# S202X.net
KiCad netlist of a schematic drawn in EAGLE
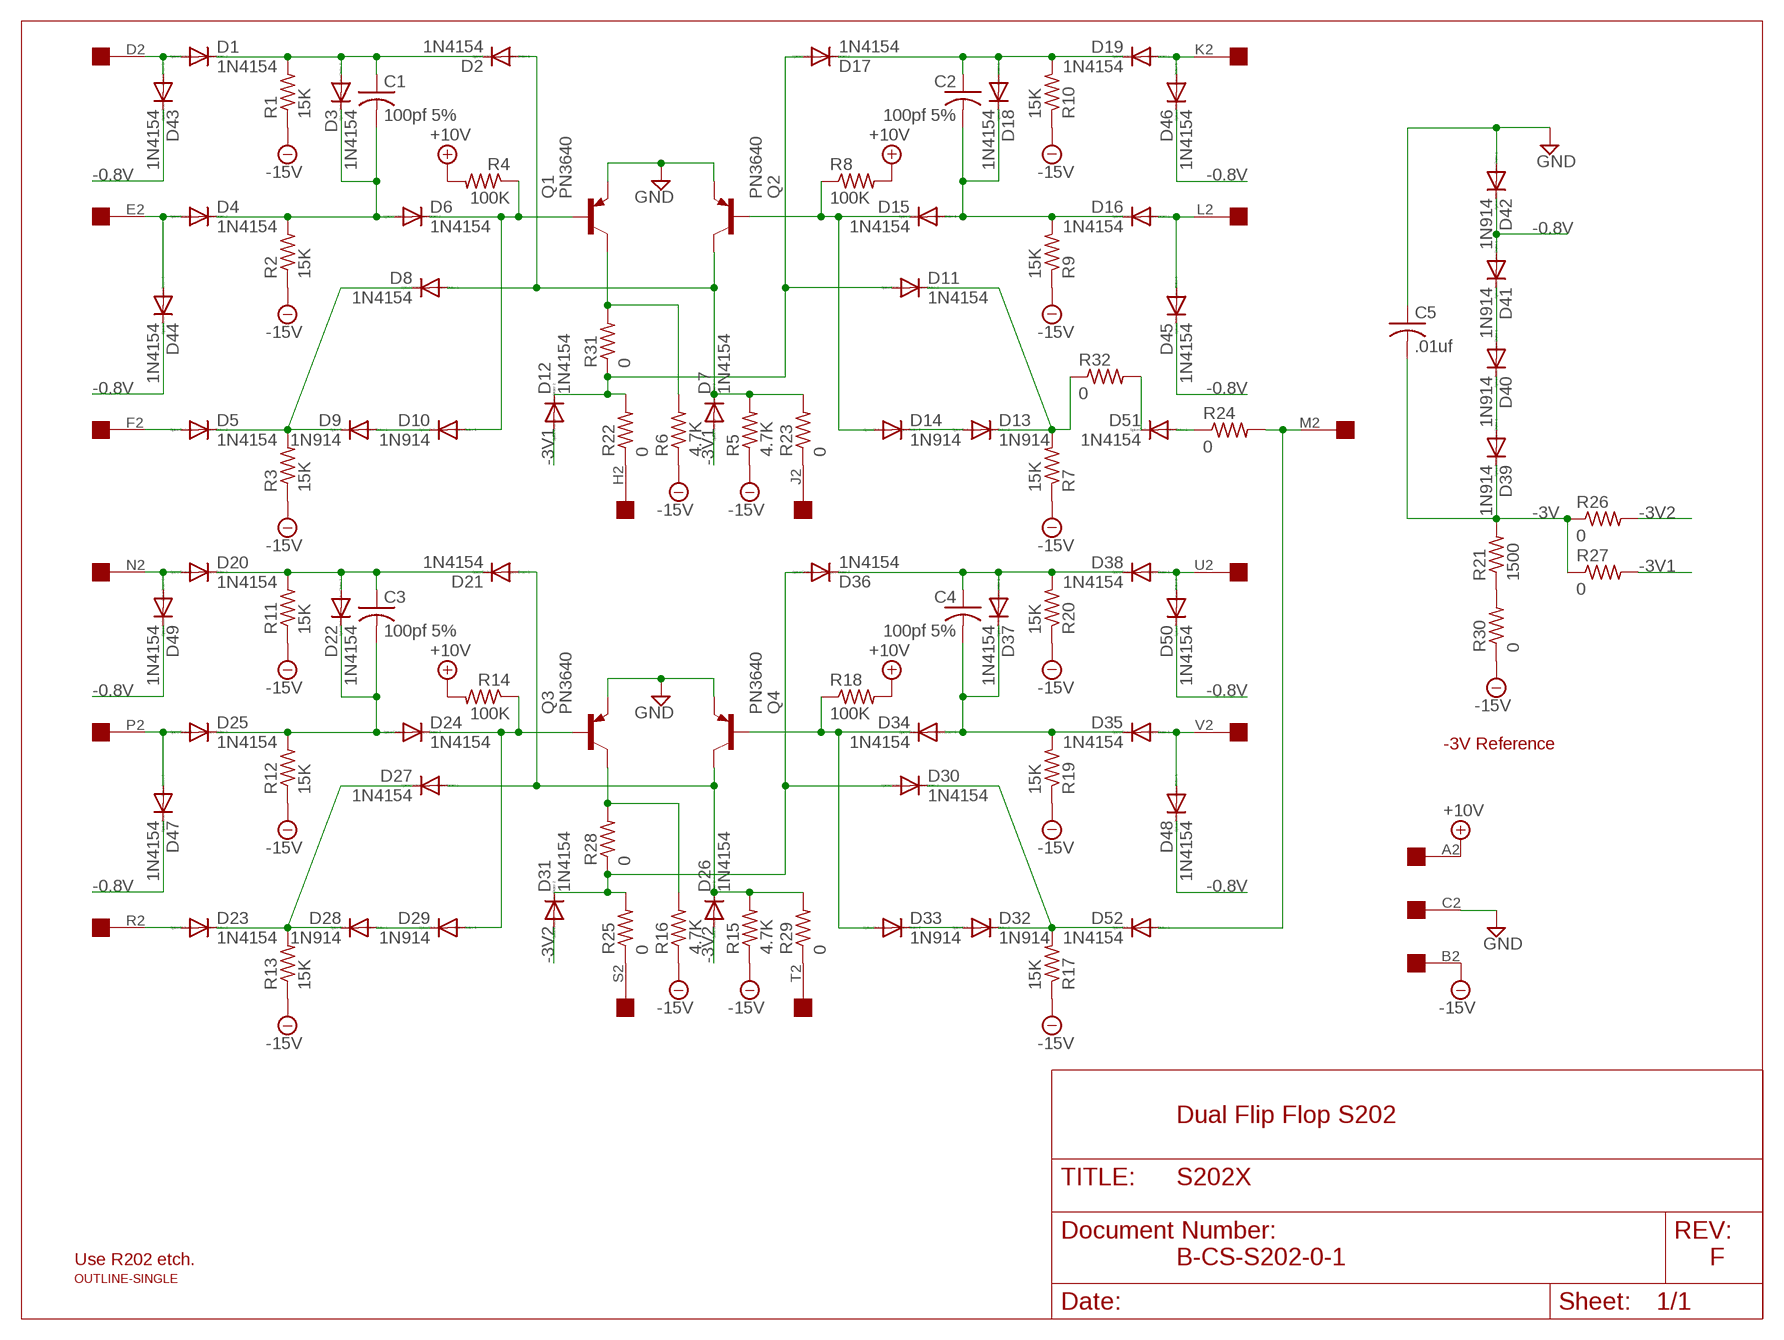
[diagram p0: schematic, sheet 1]

(export (version "E")
  (design (tool "Eeschema 10.0.6"))
  (components
    (comp (ref "C1")
      (value "100pf 5%")
      (footprint "eagle-import:C050-025X075")
      (libsource (lib "eagle-import") (part "C-US050-025X075"))
    )
    (comp (ref "C2")
      (value "100pf 5%")
      (footprint "eagle-import:C050-025X075")
      (libsource (lib "eagle-import") (part "C-US050-025X075"))
    )
    (comp (ref "C3")
      (value "100pf 5%")
      (footprint "eagle-import:C050-025X075")
      (libsource (lib "eagle-import") (part "C-US050-025X075"))
    )
    (comp (ref "C4")
      (value "100pf 5%")
      (footprint "eagle-import:C050-025X075")
      (libsource (lib "eagle-import") (part "C-US050-025X075"))
    )
    (comp (ref "C5")
      (value ".01uf")
      (footprint "eagle-import:C050-025X075")
      (libsource (lib "eagle-import") (part "C-US050-025X075"))
    )
    (comp (ref "D1")
      (value "1N4154")
      (footprint "eagle-import:DO35-10")
      (libsource (lib "eagle-import") (part "1N4148DO35-10"))
    )
    (comp (ref "D2")
      (value "1N4154")
      (footprint "eagle-import:DO35-10")
      (libsource (lib "eagle-import") (part "1N4148DO35-10"))
    )
    (comp (ref "D3")
      (value "1N4154")
      (footprint "eagle-import:DO35-10")
      (libsource (lib "eagle-import") (part "1N4148DO35-10"))
    )
    (comp (ref "D4")
      (value "1N4154")
      (footprint "eagle-import:DO35-10")
      (libsource (lib "eagle-import") (part "1N4148DO35-10"))
    )
    (comp (ref "D5")
      (value "1N4154")
      (footprint "eagle-import:DO35-10")
      (libsource (lib "eagle-import") (part "1N4148DO35-10"))
    )
    (comp (ref "D6")
      (value "1N4154")
      (footprint "eagle-import:DO35-10")
      (libsource (lib "eagle-import") (part "1N4148DO35-10"))
    )
    (comp (ref "D7")
      (value "1N4154")
      (footprint "eagle-import:DO35-10")
      (libsource (lib "eagle-import") (part "1N4148DO35-10"))
    )
    (comp (ref "D8")
      (value "1N4154")
      (footprint "eagle-import:DO35-10")
      (libsource (lib "eagle-import") (part "1N4148DO35-10"))
    )
    (comp (ref "D9")
      (value "1N914")
      (footprint "eagle-import:DO35-10")
      (libsource (lib "eagle-import") (part "1N4148DO35-10"))
    )
    (comp (ref "D10")
      (value "1N914")
      (footprint "eagle-import:DO35-10")
      (libsource (lib "eagle-import") (part "1N4148DO35-10"))
    )
    (comp (ref "D11")
      (value "1N4154")
      (footprint "eagle-import:DO35-10")
      (libsource (lib "eagle-import") (part "1N4148DO35-10"))
    )
    (comp (ref "D12")
      (value "1N4154")
      (footprint "eagle-import:DO35-10")
      (libsource (lib "eagle-import") (part "1N4148DO35-10"))
    )
    (comp (ref "D13")
      (value "1N914")
      (footprint "eagle-import:DO35-10")
      (libsource (lib "eagle-import") (part "1N4148DO35-10"))
    )
    (comp (ref "D14")
      (value "1N914")
      (footprint "eagle-import:DO35-10")
      (libsource (lib "eagle-import") (part "1N4148DO35-10"))
    )
    (comp (ref "D15")
      (value "1N4154")
      (footprint "eagle-import:DO35-10")
      (libsource (lib "eagle-import") (part "1N4148DO35-10"))
    )
    (comp (ref "D16")
      (value "1N4154")
      (footprint "eagle-import:DO35-10")
      (libsource (lib "eagle-import") (part "1N4148DO35-10"))
    )
    (comp (ref "D17")
      (value "1N4154")
      (footprint "eagle-import:DO35-10")
      (libsource (lib "eagle-import") (part "1N4148DO35-10"))
    )
    (comp (ref "D18")
      (value "1N4154")
      (footprint "eagle-import:DO35-10")
      (libsource (lib "eagle-import") (part "1N4148DO35-10"))
    )
    (comp (ref "D19")
      (value "1N4154")
      (footprint "eagle-import:DO35-10")
      (libsource (lib "eagle-import") (part "1N4148DO35-10"))
    )
    (comp (ref "D20")
      (value "1N4154")
      (footprint "eagle-import:DO35-10")
      (libsource (lib "eagle-import") (part "1N4148DO35-10"))
    )
    (comp (ref "D21")
      (value "1N4154")
      (footprint "eagle-import:DO35-10")
      (libsource (lib "eagle-import") (part "1N4148DO35-10"))
    )
    (comp (ref "D22")
      (value "1N4154")
      (footprint "eagle-import:DO35-10")
      (libsource (lib "eagle-import") (part "1N4148DO35-10"))
    )
    (comp (ref "D23")
      (value "1N4154")
      (footprint "eagle-import:DO35-10")
      (libsource (lib "eagle-import") (part "1N4148DO35-10"))
    )
    (comp (ref "D24")
      (value "1N4154")
      (footprint "eagle-import:DO35-10")
      (libsource (lib "eagle-import") (part "1N4148DO35-10"))
    )
    (comp (ref "D25")
      (value "1N4154")
      (footprint "eagle-import:DO35-10")
      (libsource (lib "eagle-import") (part "1N4148DO35-10"))
    )
    (comp (ref "D26")
      (value "1N4154")
      (footprint "eagle-import:DO35-10")
      (libsource (lib "eagle-import") (part "1N4148DO35-10"))
    )
    (comp (ref "D27")
      (value "1N4154")
      (footprint "eagle-import:DO35-10")
      (libsource (lib "eagle-import") (part "1N4148DO35-10"))
    )
    (comp (ref "D28")
      (value "1N914")
      (footprint "eagle-import:DO35-10")
      (libsource (lib "eagle-import") (part "1N4148DO35-10"))
    )
    (comp (ref "D29")
      (value "1N914")
      (footprint "eagle-import:DO35-10")
      (libsource (lib "eagle-import") (part "1N4148DO35-10"))
    )
    (comp (ref "D30")
      (value "1N4154")
      (footprint "eagle-import:DO35-10")
      (libsource (lib "eagle-import") (part "1N4148DO35-10"))
    )
    (comp (ref "D31")
      (value "1N4154")
      (footprint "eagle-import:DO35-10")
      (libsource (lib "eagle-import") (part "1N4148DO35-10"))
    )
    (comp (ref "D32")
      (value "1N914")
      (footprint "eagle-import:DO35-10")
      (libsource (lib "eagle-import") (part "1N4148DO35-10"))
    )
    (comp (ref "D33")
      (value "1N914")
      (footprint "eagle-import:DO35-10")
      (libsource (lib "eagle-import") (part "1N4148DO35-10"))
    )
    (comp (ref "D34")
      (value "1N4154")
      (footprint "eagle-import:DO35-10")
      (libsource (lib "eagle-import") (part "1N4148DO35-10"))
    )
    (comp (ref "D35")
      (value "1N4154")
      (footprint "eagle-import:DO35-10")
      (libsource (lib "eagle-import") (part "1N4148DO35-10"))
    )
    (comp (ref "D36")
      (value "1N4154")
      (footprint "eagle-import:DO35-10")
      (libsource (lib "eagle-import") (part "1N4148DO35-10"))
    )
    (comp (ref "D37")
      (value "1N4154")
      (footprint "eagle-import:DO35-10")
      (libsource (lib "eagle-import") (part "1N4148DO35-10"))
    )
    (comp (ref "D38")
      (value "1N4154")
      (footprint "eagle-import:DO35-10")
      (libsource (lib "eagle-import") (part "1N4148DO35-10"))
    )
    (comp (ref "D39")
      (value "1N914")
      (footprint "eagle-import:DO35-10")
      (libsource (lib "eagle-import") (part "1N4148DO35-10"))
    )
    (comp (ref "D40")
      (value "1N914")
      (footprint "eagle-import:DO35-10")
      (libsource (lib "eagle-import") (part "1N4148DO35-10"))
    )
    (comp (ref "D41")
      (value "1N914")
      (footprint "eagle-import:DO35-10")
      (libsource (lib "eagle-import") (part "1N4148DO35-10"))
    )
    (comp (ref "D42")
      (value "1N914")
      (footprint "eagle-import:DO35-10")
      (libsource (lib "eagle-import") (part "1N4148DO35-10"))
    )
    (comp (ref "D43")
      (value "1N4154")
      (footprint "eagle-import:DO35-10")
      (libsource (lib "eagle-import") (part "1N4148DO35-10"))
    )
    (comp (ref "D44")
      (value "1N4154")
      (footprint "eagle-import:DO35-10")
      (libsource (lib "eagle-import") (part "1N4148DO35-10"))
    )
    (comp (ref "D45")
      (value "1N4154")
      (footprint "eagle-import:DO35-10")
      (libsource (lib "eagle-import") (part "1N4148DO35-10"))
    )
    (comp (ref "D46")
      (value "1N4154")
      (footprint "eagle-import:DO35-10")
      (libsource (lib "eagle-import") (part "1N4148DO35-10"))
    )
    (comp (ref "D47")
      (value "1N4154")
      (footprint "eagle-import:DO35-10")
      (libsource (lib "eagle-import") (part "1N4148DO35-10"))
    )
    (comp (ref "D48")
      (value "1N4154")
      (footprint "eagle-import:DO35-10")
      (libsource (lib "eagle-import") (part "1N4148DO35-10"))
    )
    (comp (ref "D49")
      (value "1N4154")
      (footprint "eagle-import:DO35-10")
      (libsource (lib "eagle-import") (part "1N4148DO35-10"))
    )
    (comp (ref "D50")
      (value "1N4154")
      (footprint "eagle-import:DO35-10")
      (libsource (lib "eagle-import") (part "1N4148DO35-10"))
    )
    (comp (ref "D51")
      (value "1N4154")
      (footprint "eagle-import:DO35-10")
      (libsource (lib "eagle-import") (part "1N4148DO35-10"))
    )
    (comp (ref "D52")
      (value "1N4154")
      (footprint "eagle-import:DO35-10")
      (libsource (lib "eagle-import") (part "1N4148DO35-10"))
    )
    (comp (ref "Q1")
      (value "PN3640")
      (footprint "eagle-import:TO39")
      (libsource (lib "eagle-import") (part "2N3637"))
    )
    (comp (ref "Q2")
      (value "PN3640")
      (footprint "eagle-import:TO39")
      (libsource (lib "eagle-import") (part "2N3637"))
    )
    (comp (ref "Q3")
      (value "PN3640")
      (footprint "eagle-import:TO39")
      (libsource (lib "eagle-import") (part "2N3637"))
    )
    (comp (ref "Q4")
      (value "PN3640")
      (footprint "eagle-import:TO39")
      (libsource (lib "eagle-import") (part "2N3637"))
    )
    (comp (ref "R1")
      (value "15K")
      (footprint "eagle-import:0207_10")
      (libsource (lib "eagle-import") (part "R-US_0207/10"))
    )
    (comp (ref "R2")
      (value "15K")
      (footprint "eagle-import:0207_10")
      (libsource (lib "eagle-import") (part "R-US_0207/10"))
    )
    (comp (ref "R3")
      (value "15K")
      (footprint "eagle-import:0207_10")
      (libsource (lib "eagle-import") (part "R-US_0207/10"))
    )
    (comp (ref "R4")
      (value "100K")
      (footprint "eagle-import:0207_10")
      (libsource (lib "eagle-import") (part "R-US_0207/10"))
    )
    (comp (ref "R5")
      (value "4.7K")
      (footprint "eagle-import:0207_10")
      (libsource (lib "eagle-import") (part "R-US_0207/10"))
    )
    (comp (ref "R6")
      (value "4.7K")
      (footprint "eagle-import:0207_10")
      (libsource (lib "eagle-import") (part "R-US_0207/10"))
    )
    (comp (ref "R7")
      (value "15K")
      (footprint "eagle-import:0207_10")
      (libsource (lib "eagle-import") (part "R-US_0207/10"))
    )
    (comp (ref "R8")
      (value "100K")
      (footprint "eagle-import:0207_10")
      (libsource (lib "eagle-import") (part "R-US_0207/10"))
    )
    (comp (ref "R9")
      (value "15K")
      (footprint "eagle-import:0207_10")
      (libsource (lib "eagle-import") (part "R-US_0207/10"))
    )
    (comp (ref "R10")
      (value "15K")
      (footprint "eagle-import:0207_10")
      (libsource (lib "eagle-import") (part "R-US_0207/10"))
    )
    (comp (ref "R11")
      (value "15K")
      (footprint "eagle-import:0207_10")
      (libsource (lib "eagle-import") (part "R-US_0207/10"))
    )
    (comp (ref "R12")
      (value "15K")
      (footprint "eagle-import:0207_10")
      (libsource (lib "eagle-import") (part "R-US_0207/10"))
    )
    (comp (ref "R13")
      (value "15K")
      (footprint "eagle-import:0207_10")
      (libsource (lib "eagle-import") (part "R-US_0207/10"))
    )
    (comp (ref "R14")
      (value "100K")
      (footprint "eagle-import:0207_10")
      (libsource (lib "eagle-import") (part "R-US_0207/10"))
    )
    (comp (ref "R15")
      (value "4.7K")
      (footprint "eagle-import:0207_10")
      (libsource (lib "eagle-import") (part "R-US_0207/10"))
    )
    (comp (ref "R16")
      (value "4.7K")
      (footprint "eagle-import:0207_10")
      (libsource (lib "eagle-import") (part "R-US_0207/10"))
    )
    (comp (ref "R17")
      (value "15K")
      (footprint "eagle-import:0207_10")
      (libsource (lib "eagle-import") (part "R-US_0207/10"))
    )
    (comp (ref "R18")
      (value "100K")
      (footprint "eagle-import:0207_10")
      (libsource (lib "eagle-import") (part "R-US_0207/10"))
    )
    (comp (ref "R19")
      (value "15K")
      (footprint "eagle-import:0207_10")
      (libsource (lib "eagle-import") (part "R-US_0207/10"))
    )
    (comp (ref "R20")
      (value "15K")
      (footprint "eagle-import:0207_10")
      (libsource (lib "eagle-import") (part "R-US_0207/10"))
    )
    (comp (ref "R21")
      (value "1500")
      (footprint "eagle-import:0207_10")
      (libsource (lib "eagle-import") (part "R-US_0207/10"))
    )
    (comp (ref "R22")
      (value "0")
      (footprint "eagle-import:0207_10")
      (libsource (lib "eagle-import") (part "R-US_0207/10"))
    )
    (comp (ref "R23")
      (value "0")
      (footprint "eagle-import:0207_10")
      (libsource (lib "eagle-import") (part "R-US_0207/10"))
    )
    (comp (ref "R24")
      (value "0")
      (footprint "eagle-import:0207_10")
      (libsource (lib "eagle-import") (part "R-US_0207/10"))
    )
    (comp (ref "R25")
      (value "0")
      (footprint "eagle-import:0207_10")
      (libsource (lib "eagle-import") (part "R-US_0207/10"))
    )
    (comp (ref "R26")
      (value "0")
      (footprint "eagle-import:0207_10")
      (libsource (lib "eagle-import") (part "R-US_0207/10"))
    )
    (comp (ref "R27")
      (value "0")
      (footprint "eagle-import:0207_10")
      (libsource (lib "eagle-import") (part "R-US_0207/10"))
    )
    (comp (ref "R28")
      (value "0")
      (footprint "eagle-import:0207_10")
      (libsource (lib "eagle-import") (part "R-US_0207/10"))
    )
    (comp (ref "R29")
      (value "0")
      (footprint "eagle-import:0207_10")
      (libsource (lib "eagle-import") (part "R-US_0207/10"))
    )
    (comp (ref "R30")
      (value "0")
      (footprint "eagle-import:0207_10")
      (libsource (lib "eagle-import") (part "R-US_0207/10"))
    )
    (comp (ref "R31")
      (value "0")
      (footprint "eagle-import:0207_10")
      (libsource (lib "eagle-import") (part "R-US_0207/10"))
    )
    (comp (ref "R32")
      (value "0")
      (footprint "eagle-import:0207_10")
      (libsource (lib "eagle-import") (part "R-US_0207/10"))
    )
    (comp (ref "U$1")
      (value "OUTLINE-SINGLE")
      (footprint "eagle-import:SINGLE")
      (libsource (lib "eagle-import") (part "OUTLINE-SINGLE"))
    )
    (comp (ref "U$2")
      (value "EDGE-1")
      (footprint "eagle-import:EDGE-CON1")
      (libsource (lib "eagle-import") (part "EDGE-1"))
    )
  )
  (nets
    (net (code "1") (name "+10V") (class "Default")
      (node (ref "R14") (pin "2") (pinfunction "2_2") (pintype "passive"))
      (node (ref "R18") (pin "2") (pinfunction "2_2") (pintype "passive"))
      (node (ref "R4") (pin "2") (pinfunction "2_2") (pintype "passive"))
      (node (ref "R8") (pin "2") (pinfunction "2_2") (pintype "passive"))
      (node (ref "U$2") (pin "A2") (pinfunction "1_A2") (pintype "bidirectional"))
    )
    (net (code "2") (name "-15V") (class "Default")
      (node (ref "R1") (pin "1") (pinfunction "1_1") (pintype "passive"))
      (node (ref "R10") (pin "1") (pinfunction "1_1") (pintype "passive"))
      (node (ref "R11") (pin "1") (pinfunction "1_1") (pintype "passive"))
      (node (ref "R12") (pin "1") (pinfunction "1_1") (pintype "passive"))
      (node (ref "R13") (pin "1") (pinfunction "1_1") (pintype "passive"))
      (node (ref "R15") (pin "1") (pinfunction "1_1") (pintype "passive"))
      (node (ref "R16") (pin "1") (pinfunction "1_1") (pintype "passive"))
      (node (ref "R17") (pin "1") (pinfunction "1_1") (pintype "passive"))
      (node (ref "R19") (pin "1") (pinfunction "1_1") (pintype "passive"))
      (node (ref "R2") (pin "1") (pinfunction "1_1") (pintype "passive"))
      (node (ref "R20") (pin "1") (pinfunction "1_1") (pintype "passive"))
      (node (ref "R3") (pin "1") (pinfunction "1_1") (pintype "passive"))
      (node (ref "R30") (pin "1") (pinfunction "1_1") (pintype "passive"))
      (node (ref "R5") (pin "1") (pinfunction "1_1") (pintype "passive"))
      (node (ref "R6") (pin "1") (pinfunction "1_1") (pintype "passive"))
      (node (ref "R7") (pin "1") (pinfunction "1_1") (pintype "passive"))
      (node (ref "R9") (pin "1") (pinfunction "1_1") (pintype "passive"))
      (node (ref "U$2") (pin "B2") (pinfunction "1_B2") (pintype "bidirectional"))
    )
    (net (code "3") (name "/-0.8V") (class "Default")
      (node (ref "D41") (pin "A") (pinfunction "A_A") (pintype "passive"))
      (node (ref "D42") (pin "C") (pinfunction "C_C") (pintype "passive"))
      (node (ref "D43") (pin "C") (pinfunction "C_C") (pintype "passive"))
      (node (ref "D44") (pin "C") (pinfunction "C_C") (pintype "passive"))
      (node (ref "D45") (pin "C") (pinfunction "C_C") (pintype "passive"))
      (node (ref "D46") (pin "C") (pinfunction "C_C") (pintype "passive"))
      (node (ref "D47") (pin "C") (pinfunction "C_C") (pintype "passive"))
      (node (ref "D48") (pin "C") (pinfunction "C_C") (pintype "passive"))
      (node (ref "D49") (pin "C") (pinfunction "C_C") (pintype "passive"))
      (node (ref "D50") (pin "C") (pinfunction "C_C") (pintype "passive"))
    )
    (net (code "4") (name "/-3V") (class "Default")
      (node (ref "C5") (pin "2") (pinfunction "2_2") (pintype "passive"))
      (node (ref "D39") (pin "C") (pinfunction "C_C") (pintype "passive"))
      (node (ref "R21") (pin "2") (pinfunction "2_2") (pintype "passive"))
      (node (ref "R26") (pin "1") (pinfunction "1_1") (pintype "passive"))
      (node (ref "R27") (pin "1") (pinfunction "1_1") (pintype "passive"))
    )
    (net (code "5") (name "/-3V1") (class "Default")
      (node (ref "D12") (pin "A") (pinfunction "A_A") (pintype "passive"))
      (node (ref "D7") (pin "A") (pinfunction "A_A") (pintype "passive"))
      (node (ref "R27") (pin "2") (pinfunction "2_2") (pintype "passive"))
    )
    (net (code "6") (name "/-3V2") (class "Default")
      (node (ref "D26") (pin "A") (pinfunction "A_A") (pintype "passive"))
      (node (ref "D31") (pin "A") (pinfunction "A_A") (pintype "passive"))
      (node (ref "R26") (pin "2") (pinfunction "2_2") (pintype "passive"))
    )
    (net (code "7") (name "GND") (class "Default")
      (node (ref "C5") (pin "1") (pinfunction "1_1") (pintype "passive"))
      (node (ref "D42") (pin "A") (pinfunction "A_A") (pintype "passive"))
      (node (ref "Q1") (pin "1") (pinfunction "E_1") (pintype "passive"))
      (node (ref "Q2") (pin "1") (pinfunction "E_1") (pintype "passive"))
      (node (ref "Q3") (pin "1") (pinfunction "E_1") (pintype "passive"))
      (node (ref "Q4") (pin "1") (pinfunction "E_1") (pintype "passive"))
      (node (ref "U$2") (pin "C2") (pinfunction "1_C2") (pintype "bidirectional"))
    )
    (net (code "8") (name "Net-(C1-Pad1)") (class "Default")
      (node (ref "C1") (pin "1") (pinfunction "1_1") (pintype "passive"))
      (node (ref "D1") (pin "C") (pinfunction "C_C") (pintype "passive"))
      (node (ref "D2") (pin "C") (pinfunction "C_C") (pintype "passive"))
      (node (ref "D3") (pin "A") (pinfunction "A_A") (pintype "passive"))
      (node (ref "R1") (pin "2") (pinfunction "2_2") (pintype "passive"))
    )
    (net (code "9") (name "Net-(C1-Pad2)") (class "Default")
      (node (ref "C1") (pin "2") (pinfunction "2_2") (pintype "passive"))
      (node (ref "D3") (pin "C") (pinfunction "C_C") (pintype "passive"))
      (node (ref "D4") (pin "C") (pinfunction "C_C") (pintype "passive"))
      (node (ref "D6") (pin "A") (pinfunction "A_A") (pintype "passive"))
      (node (ref "R2") (pin "2") (pinfunction "2_2") (pintype "passive"))
    )
    (net (code "10") (name "Net-(C2-Pad1)") (class "Default")
      (node (ref "C2") (pin "1") (pinfunction "1_1") (pintype "passive"))
      (node (ref "D17") (pin "C") (pinfunction "C_C") (pintype "passive"))
      (node (ref "D18") (pin "A") (pinfunction "A_A") (pintype "passive"))
      (node (ref "D19") (pin "C") (pinfunction "C_C") (pintype "passive"))
      (node (ref "R10") (pin "2") (pinfunction "2_2") (pintype "passive"))
    )
    (net (code "11") (name "Net-(C2-Pad2)") (class "Default")
      (node (ref "C2") (pin "2") (pinfunction "2_2") (pintype "passive"))
      (node (ref "D15") (pin "A") (pinfunction "A_A") (pintype "passive"))
      (node (ref "D16") (pin "C") (pinfunction "C_C") (pintype "passive"))
      (node (ref "D18") (pin "C") (pinfunction "C_C") (pintype "passive"))
      (node (ref "R9") (pin "2") (pinfunction "2_2") (pintype "passive"))
    )
    (net (code "12") (name "Net-(C3-Pad1)") (class "Default")
      (node (ref "C3") (pin "1") (pinfunction "1_1") (pintype "passive"))
      (node (ref "D20") (pin "C") (pinfunction "C_C") (pintype "passive"))
      (node (ref "D21") (pin "C") (pinfunction "C_C") (pintype "passive"))
      (node (ref "D22") (pin "A") (pinfunction "A_A") (pintype "passive"))
      (node (ref "R11") (pin "2") (pinfunction "2_2") (pintype "passive"))
    )
    (net (code "13") (name "Net-(C3-Pad2)") (class "Default")
      (node (ref "C3") (pin "2") (pinfunction "2_2") (pintype "passive"))
      (node (ref "D22") (pin "C") (pinfunction "C_C") (pintype "passive"))
      (node (ref "D24") (pin "A") (pinfunction "A_A") (pintype "passive"))
      (node (ref "D25") (pin "C") (pinfunction "C_C") (pintype "passive"))
      (node (ref "R12") (pin "2") (pinfunction "2_2") (pintype "passive"))
    )
    (net (code "14") (name "Net-(C4-Pad1)") (class "Default")
      (node (ref "C4") (pin "1") (pinfunction "1_1") (pintype "passive"))
      (node (ref "D36") (pin "C") (pinfunction "C_C") (pintype "passive"))
      (node (ref "D37") (pin "A") (pinfunction "A_A") (pintype "passive"))
      (node (ref "D38") (pin "C") (pinfunction "C_C") (pintype "passive"))
      (node (ref "R20") (pin "2") (pinfunction "2_2") (pintype "passive"))
    )
    (net (code "15") (name "Net-(C4-Pad2)") (class "Default")
      (node (ref "C4") (pin "2") (pinfunction "2_2") (pintype "passive"))
      (node (ref "D34") (pin "A") (pinfunction "A_A") (pintype "passive"))
      (node (ref "D35") (pin "C") (pinfunction "C_C") (pintype "passive"))
      (node (ref "D37") (pin "C") (pinfunction "C_C") (pintype "passive"))
      (node (ref "R19") (pin "2") (pinfunction "2_2") (pintype "passive"))
    )
    (net (code "16") (name "Net-(D5-PadC)") (class "Default")
      (node (ref "D5") (pin "C") (pinfunction "C_C") (pintype "passive"))
      (node (ref "D8") (pin "C") (pinfunction "C_C") (pintype "passive"))
      (node (ref "D9") (pin "C") (pinfunction "C_C") (pintype "passive"))
      (node (ref "R3") (pin "2") (pinfunction "2_2") (pintype "passive"))
    )
    (net (code "17") (name "Net-(D10-PadC)") (class "Default")
      (node (ref "D10") (pin "C") (pinfunction "C_C") (pintype "passive"))
      (node (ref "D9") (pin "A") (pinfunction "A_A") (pintype "passive"))
    )
    (net (code "18") (name "Net-(D11-PadA)") (class "Default")
      (node (ref "D11") (pin "A") (pinfunction "A_A") (pintype "passive"))
      (node (ref "D12") (pin "C") (pinfunction "C_C") (pintype "passive"))
      (node (ref "D17") (pin "A") (pinfunction "A_A") (pintype "passive"))
      (node (ref "R22") (pin "2") (pinfunction "2_2") (pintype "passive"))
      (node (ref "R31") (pin "1") (pinfunction "1_1") (pintype "passive"))
    )
    (net (code "19") (name "Net-(D11-PadC)") (class "Default")
      (node (ref "D11") (pin "C") (pinfunction "C_C") (pintype "passive"))
      (node (ref "D13") (pin "C") (pinfunction "C_C") (pintype "passive"))
      (node (ref "R32") (pin "1") (pinfunction "1_1") (pintype "passive"))
      (node (ref "R7") (pin "2") (pinfunction "2_2") (pintype "passive"))
    )
    (net (code "20") (name "Net-(D13-PadA)") (class "Default")
      (node (ref "D13") (pin "A") (pinfunction "A_A") (pintype "passive"))
      (node (ref "D14") (pin "C") (pinfunction "C_C") (pintype "passive"))
    )
    (net (code "21") (name "Net-(D23-PadC)") (class "Default")
      (node (ref "D23") (pin "C") (pinfunction "C_C") (pintype "passive"))
      (node (ref "D27") (pin "C") (pinfunction "C_C") (pintype "passive"))
      (node (ref "D28") (pin "C") (pinfunction "C_C") (pintype "passive"))
      (node (ref "R13") (pin "2") (pinfunction "2_2") (pintype "passive"))
    )
    (net (code "22") (name "Net-(D28-PadA)") (class "Default")
      (node (ref "D28") (pin "A") (pinfunction "A_A") (pintype "passive"))
      (node (ref "D29") (pin "C") (pinfunction "C_C") (pintype "passive"))
    )
    (net (code "23") (name "Net-(D30-PadA)") (class "Default")
      (node (ref "D30") (pin "A") (pinfunction "A_A") (pintype "passive"))
      (node (ref "D31") (pin "C") (pinfunction "C_C") (pintype "passive"))
      (node (ref "D36") (pin "A") (pinfunction "A_A") (pintype "passive"))
      (node (ref "R25") (pin "2") (pinfunction "2_2") (pintype "passive"))
      (node (ref "R28") (pin "1") (pinfunction "1_1") (pintype "passive"))
    )
    (net (code "24") (name "Net-(D30-PadC)") (class "Default")
      (node (ref "D30") (pin "C") (pinfunction "C_C") (pintype "passive"))
      (node (ref "D32") (pin "C") (pinfunction "C_C") (pintype "passive"))
      (node (ref "D52") (pin "C") (pinfunction "C_C") (pintype "passive"))
      (node (ref "R17") (pin "2") (pinfunction "2_2") (pintype "passive"))
    )
    (net (code "25") (name "Net-(D32-PadA)") (class "Default")
      (node (ref "D32") (pin "A") (pinfunction "A_A") (pintype "passive"))
      (node (ref "D33") (pin "C") (pinfunction "C_C") (pintype "passive"))
    )
    (net (code "26") (name "Net-(D39-PadA)") (class "Default")
      (node (ref "D39") (pin "A") (pinfunction "A_A") (pintype "passive"))
      (node (ref "D40") (pin "C") (pinfunction "C_C") (pintype "passive"))
    )
    (net (code "27") (name "Net-(D40-PadA)") (class "Default")
      (node (ref "D40") (pin "A") (pinfunction "A_A") (pintype "passive"))
      (node (ref "D41") (pin "C") (pinfunction "C_C") (pintype "passive"))
    )
    (net (code "28") (name "Net-(D51-PadA)") (class "Default")
      (node (ref "D51") (pin "A") (pinfunction "A_A") (pintype "passive"))
      (node (ref "R24") (pin "1") (pinfunction "1_1") (pintype "passive"))
    )
    (net (code "29") (name "Net-(D51-PadC)") (class "Default")
      (node (ref "D51") (pin "C") (pinfunction "C_C") (pintype "passive"))
      (node (ref "R32") (pin "2") (pinfunction "2_2") (pintype "passive"))
    )
    (net (code "30") (name "Net-(Q1-B)") (class "Default")
      (node (ref "D10") (pin "A") (pinfunction "A_A") (pintype "passive"))
      (node (ref "D6") (pin "C") (pinfunction "C_C") (pintype "passive"))
      (node (ref "Q1") (pin "2") (pinfunction "B_2") (pintype "passive"))
      (node (ref "R4") (pin "1") (pinfunction "1_1") (pintype "passive"))
    )
    (net (code "31") (name "Net-(Q1-C)") (class "Default")
      (node (ref "Q1") (pin "3") (pinfunction "C_3") (pintype "passive"))
      (node (ref "R31") (pin "2") (pinfunction "2_2") (pintype "passive"))
      (node (ref "R6") (pin "2") (pinfunction "2_2") (pintype "passive"))
    )
    (net (code "32") (name "Net-(Q2-B)") (class "Default")
      (node (ref "D14") (pin "A") (pinfunction "A_A") (pintype "passive"))
      (node (ref "D15") (pin "C") (pinfunction "C_C") (pintype "passive"))
      (node (ref "Q2") (pin "2") (pinfunction "B_2") (pintype "passive"))
      (node (ref "R8") (pin "1") (pinfunction "1_1") (pintype "passive"))
    )
    (net (code "33") (name "Net-(Q2-C)") (class "Default")
      (node (ref "D2") (pin "A") (pinfunction "A_A") (pintype "passive"))
      (node (ref "D7") (pin "C") (pinfunction "C_C") (pintype "passive"))
      (node (ref "D8") (pin "A") (pinfunction "A_A") (pintype "passive"))
      (node (ref "Q2") (pin "3") (pinfunction "C_3") (pintype "passive"))
      (node (ref "R23") (pin "2") (pinfunction "2_2") (pintype "passive"))
      (node (ref "R5") (pin "2") (pinfunction "2_2") (pintype "passive"))
    )
    (net (code "34") (name "Net-(Q3-B)") (class "Default")
      (node (ref "D24") (pin "C") (pinfunction "C_C") (pintype "passive"))
      (node (ref "D29") (pin "A") (pinfunction "A_A") (pintype "passive"))
      (node (ref "Q3") (pin "2") (pinfunction "B_2") (pintype "passive"))
      (node (ref "R14") (pin "1") (pinfunction "1_1") (pintype "passive"))
    )
    (net (code "35") (name "Net-(Q3-C)") (class "Default")
      (node (ref "Q3") (pin "3") (pinfunction "C_3") (pintype "passive"))
      (node (ref "R16") (pin "2") (pinfunction "2_2") (pintype "passive"))
      (node (ref "R28") (pin "2") (pinfunction "2_2") (pintype "passive"))
    )
    (net (code "36") (name "Net-(Q4-B)") (class "Default")
      (node (ref "D33") (pin "A") (pinfunction "A_A") (pintype "passive"))
      (node (ref "D34") (pin "C") (pinfunction "C_C") (pintype "passive"))
      (node (ref "Q4") (pin "2") (pinfunction "B_2") (pintype "passive"))
      (node (ref "R18") (pin "1") (pinfunction "1_1") (pintype "passive"))
    )
    (net (code "37") (name "Net-(Q4-C)") (class "Default")
      (node (ref "D21") (pin "A") (pinfunction "A_A") (pintype "passive"))
      (node (ref "D26") (pin "C") (pinfunction "C_C") (pintype "passive"))
      (node (ref "D27") (pin "A") (pinfunction "A_A") (pintype "passive"))
      (node (ref "Q4") (pin "3") (pinfunction "C_3") (pintype "passive"))
      (node (ref "R15") (pin "2") (pinfunction "2_2") (pintype "passive"))
      (node (ref "R29") (pin "2") (pinfunction "2_2") (pintype "passive"))
    )
    (net (code "38") (name "Net-(R21-Pad1)") (class "Default")
      (node (ref "R21") (pin "1") (pinfunction "1_1") (pintype "passive"))
      (node (ref "R30") (pin "2") (pinfunction "2_2") (pintype "passive"))
    )
    (net (code "39") (name "Net-(U$2D-1)") (class "Default")
      (node (ref "D1") (pin "A") (pinfunction "A_A") (pintype "passive"))
      (node (ref "D43") (pin "A") (pinfunction "A_A") (pintype "passive"))
      (node (ref "U$2") (pin "D2") (pinfunction "1_D2") (pintype "bidirectional"))
    )
    (net (code "40") (name "Net-(U$2E-1)") (class "Default")
      (node (ref "D4") (pin "A") (pinfunction "A_A") (pintype "passive"))
      (node (ref "D44") (pin "A") (pinfunction "A_A") (pintype "passive"))
      (node (ref "U$2") (pin "E2") (pinfunction "1_E2") (pintype "bidirectional"))
    )
    (net (code "41") (name "Net-(U$2F-1)") (class "Default")
      (node (ref "D5") (pin "A") (pinfunction "A_A") (pintype "passive"))
      (node (ref "U$2") (pin "F2") (pinfunction "1_F2") (pintype "bidirectional"))
    )
    (net (code "42") (name "Net-(U$2G-1)") (class "Default")
      (node (ref "R22") (pin "1") (pinfunction "1_1") (pintype "passive"))
      (node (ref "U$2") (pin "H2") (pinfunction "1_H2") (pintype "bidirectional"))
    )
    (net (code "43") (name "Net-(U$2H-1)") (class "Default")
      (node (ref "R23") (pin "1") (pinfunction "1_1") (pintype "passive"))
      (node (ref "U$2") (pin "J2") (pinfunction "1_J2") (pintype "bidirectional"))
    )
    (net (code "44") (name "Net-(U$2I-1)") (class "Default")
      (node (ref "D19") (pin "A") (pinfunction "A_A") (pintype "passive"))
      (node (ref "D46") (pin "A") (pinfunction "A_A") (pintype "passive"))
      (node (ref "U$2") (pin "K2") (pinfunction "1_K2") (pintype "bidirectional"))
    )
    (net (code "45") (name "Net-(U$2J-1)") (class "Default")
      (node (ref "D16") (pin "A") (pinfunction "A_A") (pintype "passive"))
      (node (ref "D45") (pin "A") (pinfunction "A_A") (pintype "passive"))
      (node (ref "U$2") (pin "L2") (pinfunction "1_L2") (pintype "bidirectional"))
    )
    (net (code "46") (name "Net-(U$2K-1)") (class "Default")
      (node (ref "D52") (pin "A") (pinfunction "A_A") (pintype "passive"))
      (node (ref "R24") (pin "2") (pinfunction "2_2") (pintype "passive"))
      (node (ref "U$2") (pin "M2") (pinfunction "1_M2") (pintype "bidirectional"))
    )
    (net (code "47") (name "Net-(U$2L-1)") (class "Default")
      (node (ref "D20") (pin "A") (pinfunction "A_A") (pintype "passive"))
      (node (ref "D49") (pin "A") (pinfunction "A_A") (pintype "passive"))
      (node (ref "U$2") (pin "N2") (pinfunction "1_N2") (pintype "bidirectional"))
    )
    (net (code "48") (name "Net-(U$2M-1)") (class "Default")
      (node (ref "D25") (pin "A") (pinfunction "A_A") (pintype "passive"))
      (node (ref "D47") (pin "A") (pinfunction "A_A") (pintype "passive"))
      (node (ref "U$2") (pin "P2") (pinfunction "1_P2") (pintype "bidirectional"))
    )
    (net (code "49") (name "Net-(U$2N-1)") (class "Default")
      (node (ref "D23") (pin "A") (pinfunction "A_A") (pintype "passive"))
      (node (ref "U$2") (pin "R2") (pinfunction "1_R2") (pintype "bidirectional"))
    )
    (net (code "50") (name "Net-(U$2O-1)") (class "Default")
      (node (ref "R25") (pin "1") (pinfunction "1_1") (pintype "passive"))
      (node (ref "U$2") (pin "S2") (pinfunction "1_S2") (pintype "bidirectional"))
    )
    (net (code "51") (name "Net-(U$2P-1)") (class "Default")
      (node (ref "R29") (pin "1") (pinfunction "1_1") (pintype "passive"))
      (node (ref "U$2") (pin "T2") (pinfunction "1_T2") (pintype "bidirectional"))
    )
    (net (code "52") (name "Net-(U$2Q-1)") (class "Default")
      (node (ref "D38") (pin "A") (pinfunction "A_A") (pintype "passive"))
      (node (ref "D50") (pin "A") (pinfunction "A_A") (pintype "passive"))
      (node (ref "U$2") (pin "U2") (pinfunction "1_U2") (pintype "bidirectional"))
    )
    (net (code "53") (name "Net-(U$2R-1)") (class "Default")
      (node (ref "D35") (pin "A") (pinfunction "A_A") (pintype "passive"))
      (node (ref "D48") (pin "A") (pinfunction "A_A") (pintype "passive"))
      (node (ref "U$2") (pin "V2") (pinfunction "1_V2") (pintype "bidirectional"))
    )
  )
)
